# dacpower.net
KiCad netlist of a schematic drawn in EAGLE
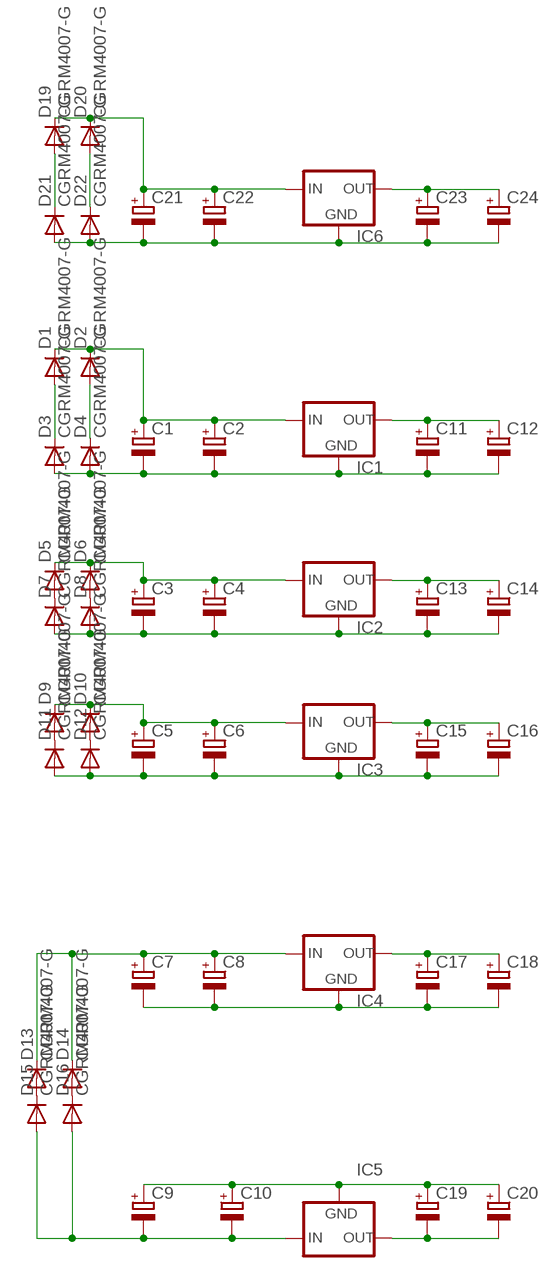
[diagram p0: schematic, sheet 1]

(export (version "E")
  (design (tool "Eeschema 10.0.6"))
  (components
    (comp (ref "C1")
      (value "CPOL-EUE7.5-18")
      (footprint "eagle-import:E7,5-18")
      (libsource (lib "eagle-import") (part "CPOL-EUE7.5-18"))
    )
    (comp (ref "C2")
      (value "CPOL-EUE7.5-18")
      (footprint "eagle-import:E7,5-18")
      (libsource (lib "eagle-import") (part "CPOL-EUE7.5-18"))
    )
    (comp (ref "C3")
      (value "CPOL-EUE7.5-18")
      (footprint "eagle-import:E7,5-18")
      (libsource (lib "eagle-import") (part "CPOL-EUE7.5-18"))
    )
    (comp (ref "C4")
      (value "CPOL-EUE7.5-18")
      (footprint "eagle-import:E7,5-18")
      (libsource (lib "eagle-import") (part "CPOL-EUE7.5-18"))
    )
    (comp (ref "C5")
      (value "CPOL-EUE7.5-18")
      (footprint "eagle-import:E7,5-18")
      (libsource (lib "eagle-import") (part "CPOL-EUE7.5-18"))
    )
    (comp (ref "C6")
      (value "CPOL-EUE7.5-18")
      (footprint "eagle-import:E7,5-18")
      (libsource (lib "eagle-import") (part "CPOL-EUE7.5-18"))
    )
    (comp (ref "C7")
      (value "CPOL-EUE7.5-18")
      (footprint "eagle-import:E7,5-18")
      (libsource (lib "eagle-import") (part "CPOL-EUE7.5-18"))
    )
    (comp (ref "C8")
      (value "CPOL-EUE7.5-18")
      (footprint "eagle-import:E7,5-18")
      (libsource (lib "eagle-import") (part "CPOL-EUE7.5-18"))
    )
    (comp (ref "C9")
      (value "CPOL-EUE7.5-18")
      (footprint "eagle-import:E7,5-18")
      (libsource (lib "eagle-import") (part "CPOL-EUE7.5-18"))
    )
    (comp (ref "C10")
      (value "CPOL-EUE7.5-18")
      (footprint "eagle-import:E7,5-18")
      (libsource (lib "eagle-import") (part "CPOL-EUE7.5-18"))
    )
    (comp (ref "C11")
      (value "CPOL-EUSP-CAP-CX")
      (footprint "eagle-import:SP-CAP-CX")
      (libsource (lib "eagle-import") (part "CPOL-EUSP-CAP-CX"))
    )
    (comp (ref "C12")
      (value "CPOL-EUSP-CAP-CX")
      (footprint "eagle-import:SP-CAP-CX")
      (libsource (lib "eagle-import") (part "CPOL-EUSP-CAP-CX"))
    )
    (comp (ref "C13")
      (value "CPOL-EUSP-CAP-CX")
      (footprint "eagle-import:SP-CAP-CX")
      (libsource (lib "eagle-import") (part "CPOL-EUSP-CAP-CX"))
    )
    (comp (ref "C14")
      (value "CPOL-EUSP-CAP-CX")
      (footprint "eagle-import:SP-CAP-CX")
      (libsource (lib "eagle-import") (part "CPOL-EUSP-CAP-CX"))
    )
    (comp (ref "C15")
      (value "CPOL-EUSP-CAP-CX")
      (footprint "eagle-import:SP-CAP-CX")
      (libsource (lib "eagle-import") (part "CPOL-EUSP-CAP-CX"))
    )
    (comp (ref "C16")
      (value "CPOL-EUSP-CAP-CX")
      (footprint "eagle-import:SP-CAP-CX")
      (libsource (lib "eagle-import") (part "CPOL-EUSP-CAP-CX"))
    )
    (comp (ref "C17")
      (value "CPOL-EUSP-CAP-CX")
      (footprint "eagle-import:SP-CAP-CX")
      (libsource (lib "eagle-import") (part "CPOL-EUSP-CAP-CX"))
    )
    (comp (ref "C18")
      (value "CPOL-EUSP-CAP-CX")
      (footprint "eagle-import:SP-CAP-CX")
      (libsource (lib "eagle-import") (part "CPOL-EUSP-CAP-CX"))
    )
    (comp (ref "C19")
      (value "CPOL-EUSP-CAP-CX")
      (footprint "eagle-import:SP-CAP-CX")
      (libsource (lib "eagle-import") (part "CPOL-EUSP-CAP-CX"))
    )
    (comp (ref "C20")
      (value "CPOL-EUSP-CAP-CX")
      (footprint "eagle-import:SP-CAP-CX")
      (libsource (lib "eagle-import") (part "CPOL-EUSP-CAP-CX"))
    )
    (comp (ref "C21")
      (value "CPOL-EUE7.5-18")
      (footprint "eagle-import:E7,5-18")
      (libsource (lib "eagle-import") (part "CPOL-EUE7.5-18"))
    )
    (comp (ref "C22")
      (value "CPOL-EUE7.5-18")
      (footprint "eagle-import:E7,5-18")
      (libsource (lib "eagle-import") (part "CPOL-EUE7.5-18"))
    )
    (comp (ref "C23")
      (value "CPOL-EUSP-CAP-CX")
      (footprint "eagle-import:SP-CAP-CX")
      (libsource (lib "eagle-import") (part "CPOL-EUSP-CAP-CX"))
    )
    (comp (ref "C24")
      (value "CPOL-EUSP-CAP-CX")
      (footprint "eagle-import:SP-CAP-CX")
      (libsource (lib "eagle-import") (part "CPOL-EUSP-CAP-CX"))
    )
    (comp (ref "D1")
      (value "CGRM4007-G")
      (footprint "eagle-import:SOD-123_MINI-SMA")
      (libsource (lib "eagle-import") (part "CGRM400-G7"))
    )
    (comp (ref "D2")
      (value "CGRM4007-G")
      (footprint "eagle-import:SOD-123_MINI-SMA")
      (libsource (lib "eagle-import") (part "CGRM400-G7"))
    )
    (comp (ref "D3")
      (value "CGRM4007-G")
      (footprint "eagle-import:SOD-123_MINI-SMA")
      (libsource (lib "eagle-import") (part "CGRM400-G7"))
    )
    (comp (ref "D4")
      (value "CGRM4007-G")
      (footprint "eagle-import:SOD-123_MINI-SMA")
      (libsource (lib "eagle-import") (part "CGRM400-G7"))
    )
    (comp (ref "D5")
      (value "CGRM4007-G")
      (footprint "eagle-import:SOD-123_MINI-SMA")
      (libsource (lib "eagle-import") (part "CGRM400-G7"))
    )
    (comp (ref "D6")
      (value "CGRM4007-G")
      (footprint "eagle-import:SOD-123_MINI-SMA")
      (libsource (lib "eagle-import") (part "CGRM400-G7"))
    )
    (comp (ref "D7")
      (value "CGRM4007-G")
      (footprint "eagle-import:SOD-123_MINI-SMA")
      (libsource (lib "eagle-import") (part "CGRM400-G7"))
    )
    (comp (ref "D8")
      (value "CGRM4007-G")
      (footprint "eagle-import:SOD-123_MINI-SMA")
      (libsource (lib "eagle-import") (part "CGRM400-G7"))
    )
    (comp (ref "D9")
      (value "CGRM4007-G")
      (footprint "eagle-import:SOD-123_MINI-SMA")
      (libsource (lib "eagle-import") (part "CGRM400-G7"))
    )
    (comp (ref "D10")
      (value "CGRM4007-G")
      (footprint "eagle-import:SOD-123_MINI-SMA")
      (libsource (lib "eagle-import") (part "CGRM400-G7"))
    )
    (comp (ref "D11")
      (value "CGRM4007-G")
      (footprint "eagle-import:SOD-123_MINI-SMA")
      (libsource (lib "eagle-import") (part "CGRM400-G7"))
    )
    (comp (ref "D12")
      (value "CGRM4007-G")
      (footprint "eagle-import:SOD-123_MINI-SMA")
      (libsource (lib "eagle-import") (part "CGRM400-G7"))
    )
    (comp (ref "D13")
      (value "CGRM4007-G")
      (footprint "eagle-import:SOD-123_MINI-SMA")
      (libsource (lib "eagle-import") (part "CGRM400-G7"))
    )
    (comp (ref "D14")
      (value "CGRM4007-G")
      (footprint "eagle-import:SOD-123_MINI-SMA")
      (libsource (lib "eagle-import") (part "CGRM400-G7"))
    )
    (comp (ref "D15")
      (value "CGRM4007-G")
      (footprint "eagle-import:SOD-123_MINI-SMA")
      (libsource (lib "eagle-import") (part "CGRM400-G7"))
    )
    (comp (ref "D16")
      (value "CGRM4007-G")
      (footprint "eagle-import:SOD-123_MINI-SMA")
      (libsource (lib "eagle-import") (part "CGRM400-G7"))
    )
    (comp (ref "D19")
      (value "CGRM4007-G")
      (footprint "eagle-import:SOD-123_MINI-SMA")
      (libsource (lib "eagle-import") (part "CGRM400-G7"))
    )
    (comp (ref "D20")
      (value "CGRM4007-G")
      (footprint "eagle-import:SOD-123_MINI-SMA")
      (libsource (lib "eagle-import") (part "CGRM400-G7"))
    )
    (comp (ref "D21")
      (value "CGRM4007-G")
      (footprint "eagle-import:SOD-123_MINI-SMA")
      (libsource (lib "eagle-import") (part "CGRM400-G7"))
    )
    (comp (ref "D22")
      (value "CGRM4007-G")
      (footprint "eagle-import:SOD-123_MINI-SMA")
      (libsource (lib "eagle-import") (part "CGRM400-G7"))
    )
    (comp (ref "IC1")
      (value "78XXS")
      (footprint "eagle-import:78XXS")
      (libsource (lib "eagle-import") (part "78XXS"))
    )
    (comp (ref "IC2")
      (value "78XXS")
      (footprint "eagle-import:78XXS")
      (libsource (lib "eagle-import") (part "78XXS"))
    )
    (comp (ref "IC3")
      (value "78XXS")
      (footprint "eagle-import:78XXS")
      (libsource (lib "eagle-import") (part "78XXS"))
    )
    (comp (ref "IC4")
      (value "78XXS")
      (footprint "eagle-import:78XXS")
      (libsource (lib "eagle-import") (part "78XXS"))
    )
    (comp (ref "IC5")
      (value "79XXS")
      (footprint "eagle-import:79XXS")
      (libsource (lib "eagle-import") (part "79XXS"))
    )
    (comp (ref "IC6")
      (value "78XXS")
      (footprint "eagle-import:78XXS")
      (libsource (lib "eagle-import") (part "78XXS"))
    )
  )
  (nets
    (net (code "1") (name "Net-(C1-Pad+)") (class "Default")
      (node (ref "C1") (pin "+") (pinfunction "+_+") (pintype "passive"))
      (node (ref "C2") (pin "+") (pinfunction "+_+") (pintype "passive"))
      (node (ref "D1") (pin "C") (pinfunction "C_C") (pintype "passive"))
      (node (ref "D2") (pin "C") (pinfunction "C_C") (pintype "passive"))
      (node (ref "IC1") (pin "IN") (pinfunction "IN_IN") (pintype "input"))
    )
    (net (code "2") (name "Net-(C1-Pad-)") (class "Default")
      (node (ref "C1") (pin "-") (pinfunction "-_-") (pintype "passive"))
      (node (ref "C11") (pin "-") (pinfunction "-_-") (pintype "passive"))
      (node (ref "C12") (pin "-") (pinfunction "-_-") (pintype "passive"))
      (node (ref "C2") (pin "-") (pinfunction "-_-") (pintype "passive"))
      (node (ref "D3") (pin "A") (pinfunction "A_A") (pintype "passive"))
      (node (ref "D4") (pin "A") (pinfunction "A_A") (pintype "passive"))
      (node (ref "IC1") (pin "GND") (pinfunction "GND_GND") (pintype "input"))
    )
    (net (code "3") (name "Net-(C3-Pad+)") (class "Default")
      (node (ref "C3") (pin "+") (pinfunction "+_+") (pintype "passive"))
      (node (ref "C4") (pin "+") (pinfunction "+_+") (pintype "passive"))
      (node (ref "D5") (pin "C") (pinfunction "C_C") (pintype "passive"))
      (node (ref "D6") (pin "C") (pinfunction "C_C") (pintype "passive"))
      (node (ref "IC2") (pin "IN") (pinfunction "IN_IN") (pintype "input"))
    )
    (net (code "4") (name "Net-(C5-Pad+)") (class "Default")
      (node (ref "C5") (pin "+") (pinfunction "+_+") (pintype "passive"))
      (node (ref "C6") (pin "+") (pinfunction "+_+") (pintype "passive"))
      (node (ref "D10") (pin "C") (pinfunction "C_C") (pintype "passive"))
      (node (ref "D9") (pin "C") (pinfunction "C_C") (pintype "passive"))
      (node (ref "IC3") (pin "IN") (pinfunction "IN_IN") (pintype "input"))
    )
    (net (code "5") (name "Net-(C7-Pad+)") (class "Default")
      (node (ref "C7") (pin "+") (pinfunction "+_+") (pintype "passive"))
      (node (ref "C8") (pin "+") (pinfunction "+_+") (pintype "passive"))
      (node (ref "D13") (pin "C") (pinfunction "C_C") (pintype "passive"))
      (node (ref "D14") (pin "C") (pinfunction "C_C") (pintype "passive"))
      (node (ref "IC4") (pin "IN") (pinfunction "IN_IN") (pintype "input"))
    )
    (net (code "6") (name "Net-(C10-Pad+)") (class "Default")
      (node (ref "C10") (pin "+") (pinfunction "+_+") (pintype "passive"))
      (node (ref "C19") (pin "+") (pinfunction "+_+") (pintype "passive"))
      (node (ref "C20") (pin "+") (pinfunction "+_+") (pintype "passive"))
      (node (ref "C9") (pin "+") (pinfunction "+_+") (pintype "passive"))
      (node (ref "IC5") (pin "GND") (pinfunction "GND_GND") (pintype "input"))
    )
    (net (code "7") (name "Net-(C10-Pad-)") (class "Default")
      (node (ref "C10") (pin "-") (pinfunction "-_-") (pintype "passive"))
      (node (ref "C9") (pin "-") (pinfunction "-_-") (pintype "passive"))
      (node (ref "D15") (pin "A") (pinfunction "A_A") (pintype "passive"))
      (node (ref "D16") (pin "A") (pinfunction "A_A") (pintype "passive"))
      (node (ref "IC5") (pin "IN") (pinfunction "IN_IN") (pintype "input"))
    )
    (net (code "8") (name "Net-(C11-Pad+)") (class "Default")
      (node (ref "C11") (pin "+") (pinfunction "+_+") (pintype "passive"))
      (node (ref "C12") (pin "+") (pinfunction "+_+") (pintype "passive"))
      (node (ref "IC1") (pin "OUT") (pinfunction "OUT_OUT") (pintype "passive"))
    )
    (net (code "9") (name "Net-(C13-Pad+)") (class "Default")
      (node (ref "C13") (pin "+") (pinfunction "+_+") (pintype "passive"))
      (node (ref "C14") (pin "+") (pinfunction "+_+") (pintype "passive"))
      (node (ref "IC2") (pin "OUT") (pinfunction "OUT_OUT") (pintype "passive"))
    )
    (net (code "10") (name "Net-(C13-Pad-)") (class "Default")
      (node (ref "C13") (pin "-") (pinfunction "-_-") (pintype "passive"))
      (node (ref "C14") (pin "-") (pinfunction "-_-") (pintype "passive"))
      (node (ref "C3") (pin "-") (pinfunction "-_-") (pintype "passive"))
      (node (ref "C4") (pin "-") (pinfunction "-_-") (pintype "passive"))
      (node (ref "D7") (pin "A") (pinfunction "A_A") (pintype "passive"))
      (node (ref "D8") (pin "A") (pinfunction "A_A") (pintype "passive"))
      (node (ref "IC2") (pin "GND") (pinfunction "GND_GND") (pintype "input"))
    )
    (net (code "11") (name "Net-(C15-Pad+)") (class "Default")
      (node (ref "C15") (pin "+") (pinfunction "+_+") (pintype "passive"))
      (node (ref "C16") (pin "+") (pinfunction "+_+") (pintype "passive"))
      (node (ref "IC3") (pin "OUT") (pinfunction "OUT_OUT") (pintype "passive"))
    )
    (net (code "12") (name "Net-(C15-Pad-)") (class "Default")
      (node (ref "C15") (pin "-") (pinfunction "-_-") (pintype "passive"))
      (node (ref "C16") (pin "-") (pinfunction "-_-") (pintype "passive"))
      (node (ref "C5") (pin "-") (pinfunction "-_-") (pintype "passive"))
      (node (ref "C6") (pin "-") (pinfunction "-_-") (pintype "passive"))
      (node (ref "D11") (pin "A") (pinfunction "A_A") (pintype "passive"))
      (node (ref "D12") (pin "A") (pinfunction "A_A") (pintype "passive"))
      (node (ref "IC3") (pin "GND") (pinfunction "GND_GND") (pintype "input"))
    )
    (net (code "13") (name "Net-(C17-Pad+)") (class "Default")
      (node (ref "C17") (pin "+") (pinfunction "+_+") (pintype "passive"))
      (node (ref "C18") (pin "+") (pinfunction "+_+") (pintype "passive"))
      (node (ref "IC4") (pin "OUT") (pinfunction "OUT_OUT") (pintype "passive"))
    )
    (net (code "14") (name "Net-(C17-Pad-)") (class "Default")
      (node (ref "C17") (pin "-") (pinfunction "-_-") (pintype "passive"))
      (node (ref "C18") (pin "-") (pinfunction "-_-") (pintype "passive"))
      (node (ref "C7") (pin "-") (pinfunction "-_-") (pintype "passive"))
      (node (ref "C8") (pin "-") (pinfunction "-_-") (pintype "passive"))
      (node (ref "IC4") (pin "GND") (pinfunction "GND_GND") (pintype "input"))
    )
    (net (code "15") (name "Net-(C19-Pad-)") (class "Default")
      (node (ref "C19") (pin "-") (pinfunction "-_-") (pintype "passive"))
      (node (ref "C20") (pin "-") (pinfunction "-_-") (pintype "passive"))
      (node (ref "IC5") (pin "OUT") (pinfunction "OUT_OUT") (pintype "passive"))
    )
    (net (code "16") (name "Net-(C21-Pad+)") (class "Default")
      (node (ref "C21") (pin "+") (pinfunction "+_+") (pintype "passive"))
      (node (ref "C22") (pin "+") (pinfunction "+_+") (pintype "passive"))
      (node (ref "D19") (pin "C") (pinfunction "C_C") (pintype "passive"))
      (node (ref "D20") (pin "C") (pinfunction "C_C") (pintype "passive"))
      (node (ref "IC6") (pin "IN") (pinfunction "IN_IN") (pintype "input"))
    )
    (net (code "17") (name "Net-(C21-Pad-)") (class "Default")
      (node (ref "C21") (pin "-") (pinfunction "-_-") (pintype "passive"))
      (node (ref "C22") (pin "-") (pinfunction "-_-") (pintype "passive"))
      (node (ref "C23") (pin "-") (pinfunction "-_-") (pintype "passive"))
      (node (ref "C24") (pin "-") (pinfunction "-_-") (pintype "passive"))
      (node (ref "D21") (pin "A") (pinfunction "A_A") (pintype "passive"))
      (node (ref "D22") (pin "A") (pinfunction "A_A") (pintype "passive"))
      (node (ref "IC6") (pin "GND") (pinfunction "GND_GND") (pintype "input"))
    )
    (net (code "18") (name "Net-(C23-Pad+)") (class "Default")
      (node (ref "C23") (pin "+") (pinfunction "+_+") (pintype "passive"))
      (node (ref "C24") (pin "+") (pinfunction "+_+") (pintype "passive"))
      (node (ref "IC6") (pin "OUT") (pinfunction "OUT_OUT") (pintype "passive"))
    )
    (net (code "19") (name "Net-(D1-PadA)") (class "Default")
      (node (ref "D1") (pin "A") (pinfunction "A_A") (pintype "passive"))
      (node (ref "D3") (pin "C") (pinfunction "C_C") (pintype "passive"))
    )
    (net (code "20") (name "Net-(D2-PadA)") (class "Default")
      (node (ref "D2") (pin "A") (pinfunction "A_A") (pintype "passive"))
      (node (ref "D4") (pin "C") (pinfunction "C_C") (pintype "passive"))
    )
    (net (code "21") (name "Net-(D5-PadA)") (class "Default")
      (node (ref "D5") (pin "A") (pinfunction "A_A") (pintype "passive"))
      (node (ref "D7") (pin "C") (pinfunction "C_C") (pintype "passive"))
    )
    (net (code "22") (name "Net-(D6-PadA)") (class "Default")
      (node (ref "D6") (pin "A") (pinfunction "A_A") (pintype "passive"))
      (node (ref "D8") (pin "C") (pinfunction "C_C") (pintype "passive"))
    )
    (net (code "23") (name "Net-(D10-PadA)") (class "Default")
      (node (ref "D10") (pin "A") (pinfunction "A_A") (pintype "passive"))
      (node (ref "D12") (pin "C") (pinfunction "C_C") (pintype "passive"))
    )
    (net (code "24") (name "Net-(D11-PadC)") (class "Default")
      (node (ref "D11") (pin "C") (pinfunction "C_C") (pintype "passive"))
      (node (ref "D9") (pin "A") (pinfunction "A_A") (pintype "passive"))
    )
    (net (code "25") (name "Net-(D13-PadA)") (class "Default")
      (node (ref "D13") (pin "A") (pinfunction "A_A") (pintype "passive"))
      (node (ref "D15") (pin "C") (pinfunction "C_C") (pintype "passive"))
    )
    (net (code "26") (name "Net-(D14-PadA)") (class "Default")
      (node (ref "D14") (pin "A") (pinfunction "A_A") (pintype "passive"))
      (node (ref "D16") (pin "C") (pinfunction "C_C") (pintype "passive"))
    )
    (net (code "27") (name "Net-(D19-PadA)") (class "Default")
      (node (ref "D19") (pin "A") (pinfunction "A_A") (pintype "passive"))
      (node (ref "D21") (pin "C") (pinfunction "C_C") (pintype "passive"))
    )
    (net (code "28") (name "Net-(D20-PadA)") (class "Default")
      (node (ref "D20") (pin "A") (pinfunction "A_A") (pintype "passive"))
      (node (ref "D22") (pin "C") (pinfunction "C_C") (pintype "passive"))
    )
  )
)
